# logique_hardware.net
KiCad netlist of a schematic drawn in Altium Designer
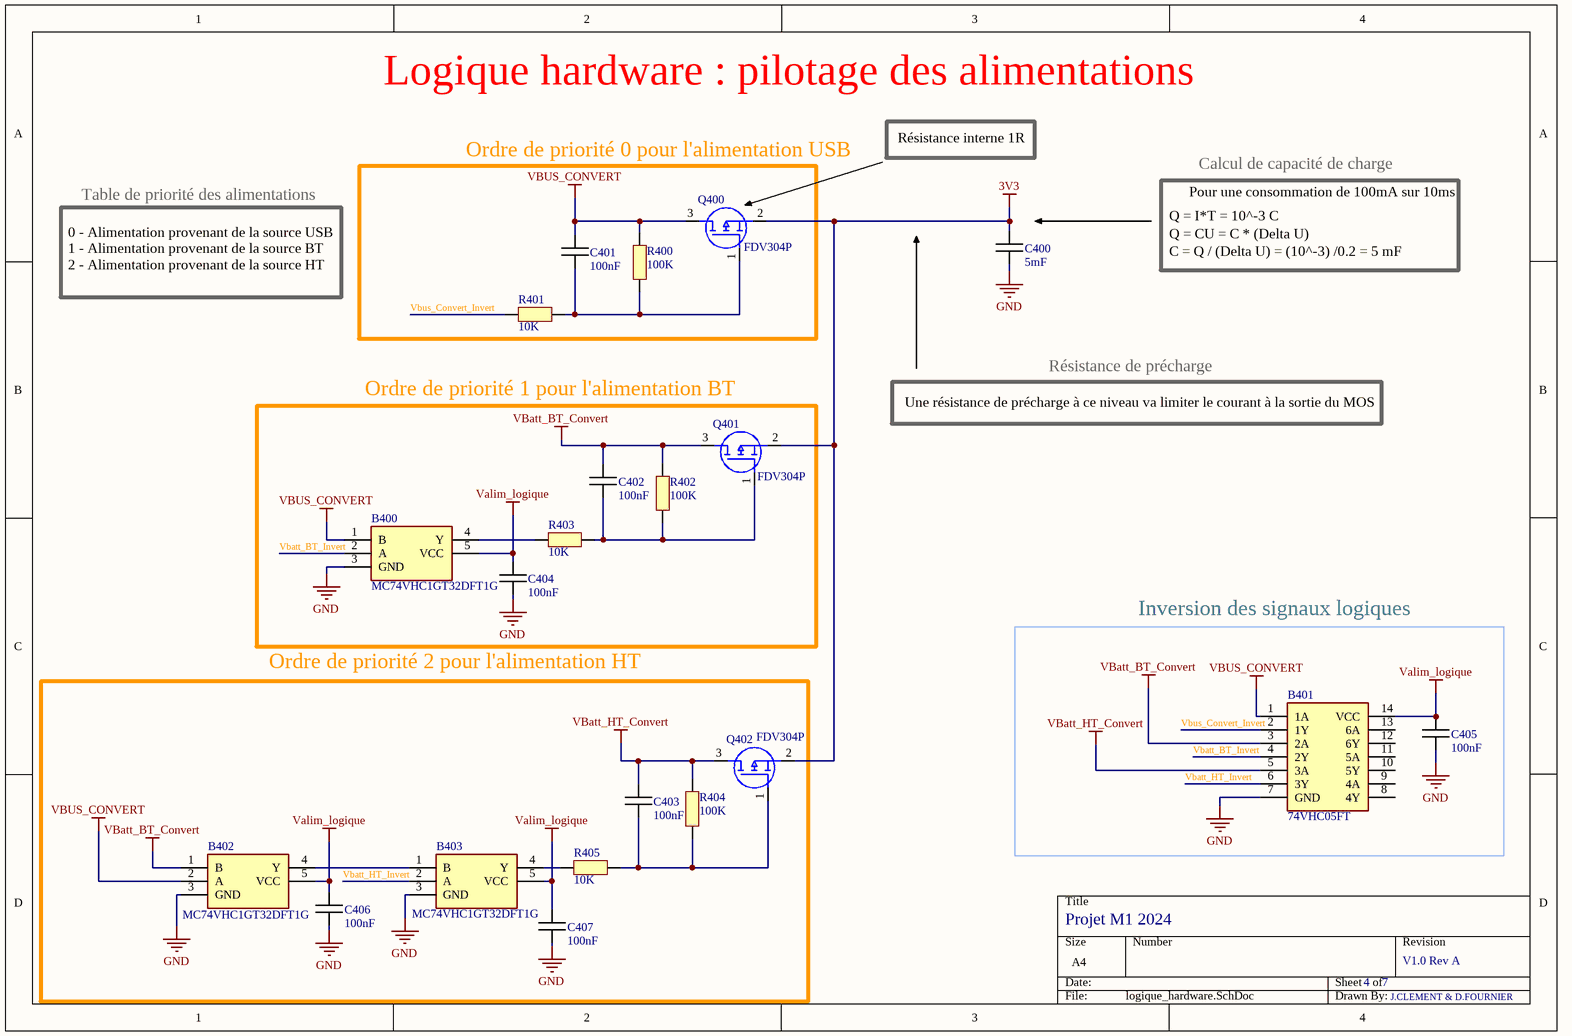
[diagram p0: logique_hardware.SchDoc]

(export (version "E")
  (design (tool "Eeschema 10.0.6"))
  (components
    (comp (ref "B400")
      (value "MC74VHC1GT32DFT1G")
      (footprint "SOT65P210X110-5N")
      (description "Single 2-Input OR Gate, TTL Level")
      (fields (field (name "MOUSER PART NUMBER") "863-C74VHC1GT32DFT1G"))
      (libsource (lib "SCHLibrary") (part "MC74VHC1GT32DFT1G"))
    )
    (comp (ref "B401")
      (value "74VHC05FT")
      (footprint "SOP65P640X120-14N")
      (description "Logic Gates CMOS LOGIC IC INVERTER")
      (fields (field (name "MOUSER PART NUMBER") "757-74VHC05FT"))
      (libsource (lib "SCHLibrary") (part "74VHC05FT"))
    )
    (comp (ref "B402")
      (value "MC74VHC1GT32DFT1G")
      (footprint "SOT65P210X110-5N")
      (description "Single 2-Input OR Gate, TTL Level")
      (fields (field (name "MOUSER PART NUMBER") "863-C74VHC1GT32DFT1G"))
      (libsource (lib "SCHLibrary") (part "MC74VHC1GT32DFT1G"))
    )
    (comp (ref "B403")
      (value "MC74VHC1GT32DFT1G")
      (footprint "SOT65P210X110-5N")
      (description "Single 2-Input OR Gate, TTL Level")
      (fields (field (name "MOUSER PART NUMBER") "863-C74VHC1GT32DFT1G"))
      (libsource (lib "SCHLibrary") (part "MC74VHC1GT32DFT1G"))
    )
    (comp (ref "C400")
      (value "5mF")
      (footprint "CAPA_0603")
      (libsource (lib "SCHLibrary") (part "Capacitor"))
    )
    (comp (ref "C401")
      (value "100nF")
      (footprint "CAPA_0603")
      (libsource (lib "SCHLibrary") (part "Capacitor"))
    )
    (comp (ref "C402")
      (value "100nF")
      (footprint "CAPA_0603")
      (libsource (lib "SCHLibrary") (part "Capacitor"))
    )
    (comp (ref "C403")
      (value "100nF")
      (footprint "CAPA_0603")
      (libsource (lib "SCHLibrary") (part "Capacitor"))
    )
    (comp (ref "C404")
      (value "100nF")
      (footprint "CAPA_0603")
      (libsource (lib "SCHLibrary") (part "Capacitor"))
    )
    (comp (ref "C405")
      (value "100nF")
      (footprint "CAPA_0603")
      (libsource (lib "SCHLibrary") (part "Capacitor"))
    )
    (comp (ref "C406")
      (value "100nF")
      (footprint "CAPA_0603")
      (libsource (lib "SCHLibrary") (part "Capacitor"))
    )
    (comp (ref "C407")
      (value "100nF")
      (footprint "CAPA_0603")
      (libsource (lib "SCHLibrary") (part "Capacitor"))
    )
    (comp (ref "Q400")
      (value "FDV304P")
      (footprint "SOT95P251X112-3N")
      (fields (field (name "MOUSER PART NUMBER") "512-FDV304P"))
      (libsource (lib "SCHLibrary") (part "FDV304P"))
    )
    (comp (ref "Q401")
      (value "FDV304P")
      (footprint "SOT95P251X112-3N")
      (fields (field (name "MOUSER PART NUMBER") "512-FDV304P"))
      (libsource (lib "SCHLibrary") (part "FDV304P"))
    )
    (comp (ref "Q402")
      (value "FDV304P")
      (footprint "SOT95P251X112-3N")
      (fields (field (name "MOUSER PART NUMBER") "512-FDV304P"))
      (libsource (lib "SCHLibrary") (part "FDV304P"))
    )
    (comp (ref "R400") (value "100K") (footprint "RES_0603") (libsource (lib "") (part "Resistor_1")))
    (comp (ref "R401") (value "10K") (footprint "RES_0603") (libsource (lib "SCHLibrary") (part "Resistor")))
    (comp (ref "R402") (value "100K") (footprint "RES_0603") (libsource (lib "") (part "Resistor_1")))
    (comp (ref "R403") (value "10K") (footprint "RES_0603") (libsource (lib "SCHLibrary") (part "Resistor")))
    (comp (ref "R404") (value "100K") (footprint "RES_0603") (libsource (lib "") (part "Resistor_1")))
    (comp (ref "R405") (value "10K") (footprint "RES_0603") (libsource (lib "SCHLibrary") (part "Resistor")))
  )
  (nets
    (net (code "1") (name "/Vbatt_BT_Invert") (class "Default")
      (node (ref "B400") (pin "2") (pinfunction "A_2") (pintype "passive"))
      (node (ref "B401") (pin "4") (pinfunction "2Y_4") (pintype "passive"))
    )
    (net (code "2") (name "/Vbatt_HT_Invert") (class "Default")
      (node (ref "B401") (pin "6") (pinfunction "3Y_6") (pintype "passive"))
      (node (ref "B403") (pin "2") (pinfunction "A_2") (pintype "passive"))
    )
    (net (code "3") (name "/Vbus_Convert_Invert") (class "Default")
      (node (ref "B401") (pin "2") (pinfunction "1Y_2") (pintype "passive"))
      (node (ref "R401") (pin "1") (pinfunction "1_1") (pintype "passive"))
    )
    (net (code "4") (name "3V3") (class "Default")
      (node (ref "C400") (pin "1") (pinfunction "1_1") (pintype "passive"))
      (node (ref "Q400") (pin "2") (pinfunction "S_2") (pintype "passive"))
      (node (ref "Q401") (pin "2") (pinfunction "S_2") (pintype "passive"))
      (node (ref "Q402") (pin "2") (pinfunction "S_2") (pintype "passive"))
    )
    (net (code "5") (name "GND") (class "Default")
      (node (ref "B400") (pin "3") (pinfunction "GND_3") (pintype "passive"))
      (node (ref "B401") (pin "7") (pinfunction "GND_7") (pintype "passive"))
      (node (ref "B402") (pin "3") (pinfunction "GND_3") (pintype "passive"))
      (node (ref "B403") (pin "3") (pinfunction "GND_3") (pintype "passive"))
      (node (ref "C400") (pin "2") (pinfunction "2_2") (pintype "passive"))
      (node (ref "C404") (pin "2") (pinfunction "2_2") (pintype "passive"))
      (node (ref "C405") (pin "2") (pinfunction "2_2") (pintype "passive"))
      (node (ref "C406") (pin "2") (pinfunction "2_2") (pintype "passive"))
      (node (ref "C407") (pin "2") (pinfunction "2_2") (pintype "passive"))
    )
    (net (code "6") (name "Net-(B400-Y)") (class "Default")
      (node (ref "B400") (pin "4") (pinfunction "Y_4") (pintype "passive"))
      (node (ref "R403") (pin "1") (pinfunction "1_1") (pintype "passive"))
    )
    (net (code "7") (name "Net-(B402-Y)") (class "Default")
      (node (ref "B402") (pin "4") (pinfunction "Y_4") (pintype "passive"))
      (node (ref "B403") (pin "1") (pinfunction "B_1") (pintype "passive"))
    )
    (net (code "8") (name "Net-(B403-Y)") (class "Default")
      (node (ref "B403") (pin "4") (pinfunction "Y_4") (pintype "passive"))
      (node (ref "R405") (pin "1") (pinfunction "1_1") (pintype "passive"))
    )
    (net (code "9") (name "Net-(Q400-G)") (class "Default")
      (node (ref "C401") (pin "2") (pinfunction "2_2") (pintype "passive"))
      (node (ref "Q400") (pin "1") (pinfunction "G_1") (pintype "passive"))
      (node (ref "R400") (pin "1") (pinfunction "1_1") (pintype "passive"))
      (node (ref "R401") (pin "2") (pinfunction "2_2") (pintype "passive"))
    )
    (net (code "10") (name "Net-(Q401-G)") (class "Default")
      (node (ref "C402") (pin "2") (pinfunction "2_2") (pintype "passive"))
      (node (ref "Q401") (pin "1") (pinfunction "G_1") (pintype "passive"))
      (node (ref "R402") (pin "1") (pinfunction "1_1") (pintype "passive"))
      (node (ref "R403") (pin "2") (pinfunction "2_2") (pintype "passive"))
    )
    (net (code "11") (name "Net-(Q402-G)") (class "Default")
      (node (ref "C403") (pin "2") (pinfunction "2_2") (pintype "passive"))
      (node (ref "Q402") (pin "1") (pinfunction "G_1") (pintype "passive"))
      (node (ref "R404") (pin "1") (pinfunction "1_1") (pintype "passive"))
      (node (ref "R405") (pin "2") (pinfunction "2_2") (pintype "passive"))
    )
    (net (code "12") (name "VBUS_CONVERT") (class "Default")
      (node (ref "B400") (pin "1") (pinfunction "B_1") (pintype "passive"))
      (node (ref "B401") (pin "1") (pinfunction "1A_1") (pintype "passive"))
      (node (ref "B402") (pin "2") (pinfunction "A_2") (pintype "passive"))
      (node (ref "C401") (pin "1") (pinfunction "1_1") (pintype "passive"))
      (node (ref "Q400") (pin "3") (pinfunction "D_3") (pintype "passive"))
      (node (ref "R400") (pin "2") (pinfunction "2_2") (pintype "passive"))
    )
    (net (code "13") (name "VBatt_BT_Convert") (class "Default")
      (node (ref "B401") (pin "3") (pinfunction "2A_3") (pintype "passive"))
      (node (ref "B402") (pin "1") (pinfunction "B_1") (pintype "passive"))
      (node (ref "C402") (pin "1") (pinfunction "1_1") (pintype "passive"))
      (node (ref "Q401") (pin "3") (pinfunction "D_3") (pintype "passive"))
      (node (ref "R402") (pin "2") (pinfunction "2_2") (pintype "passive"))
    )
    (net (code "14") (name "VBatt_HT_Convert") (class "Default")
      (node (ref "B401") (pin "5") (pinfunction "3A_5") (pintype "passive"))
      (node (ref "C403") (pin "1") (pinfunction "1_1") (pintype "passive"))
      (node (ref "Q402") (pin "3") (pinfunction "D_3") (pintype "passive"))
      (node (ref "R404") (pin "2") (pinfunction "2_2") (pintype "passive"))
    )
    (net (code "15") (name "Valim_logique") (class "Default")
      (node (ref "B400") (pin "5") (pinfunction "VCC_5") (pintype "passive"))
      (node (ref "B401") (pin "14") (pinfunction "VCC_14") (pintype "passive"))
      (node (ref "B402") (pin "5") (pinfunction "VCC_5") (pintype "passive"))
      (node (ref "B403") (pin "5") (pinfunction "VCC_5") (pintype "passive"))
      (node (ref "C404") (pin "1") (pinfunction "1_1") (pintype "passive"))
      (node (ref "C405") (pin "1") (pinfunction "1_1") (pintype "passive"))
      (node (ref "C406") (pin "1") (pinfunction "1_1") (pintype "passive"))
      (node (ref "C407") (pin "1") (pinfunction "1_1") (pintype "passive"))
    )
    (net (code "16") (name "unconnected-(B401-4A-Pad9)") (class "Default")
      (node (ref "B401") (pin "9") (pinfunction "4A_9") (pintype "passive"))
    )
    (net (code "17") (name "unconnected-(B401-4Y-Pad8)") (class "Default")
      (node (ref "B401") (pin "8") (pinfunction "4Y_8") (pintype "passive"))
    )
    (net (code "18") (name "unconnected-(B401-5A-Pad11)") (class "Default")
      (node (ref "B401") (pin "11") (pinfunction "5A_11") (pintype "passive"))
    )
    (net (code "19") (name "unconnected-(B401-5Y-Pad10)") (class "Default")
      (node (ref "B401") (pin "10") (pinfunction "5Y_10") (pintype "passive"))
    )
    (net (code "20") (name "unconnected-(B401-6A-Pad13)") (class "Default")
      (node (ref "B401") (pin "13") (pinfunction "6A_13") (pintype "passive"))
    )
    (net (code "21") (name "unconnected-(B401-6Y-Pad12)") (class "Default")
      (node (ref "B401") (pin "12") (pinfunction "6Y_12") (pintype "passive"))
    )
  )
)
